# Upper_Board.net
KiCad netlist of a schematic drawn in Altium Designer
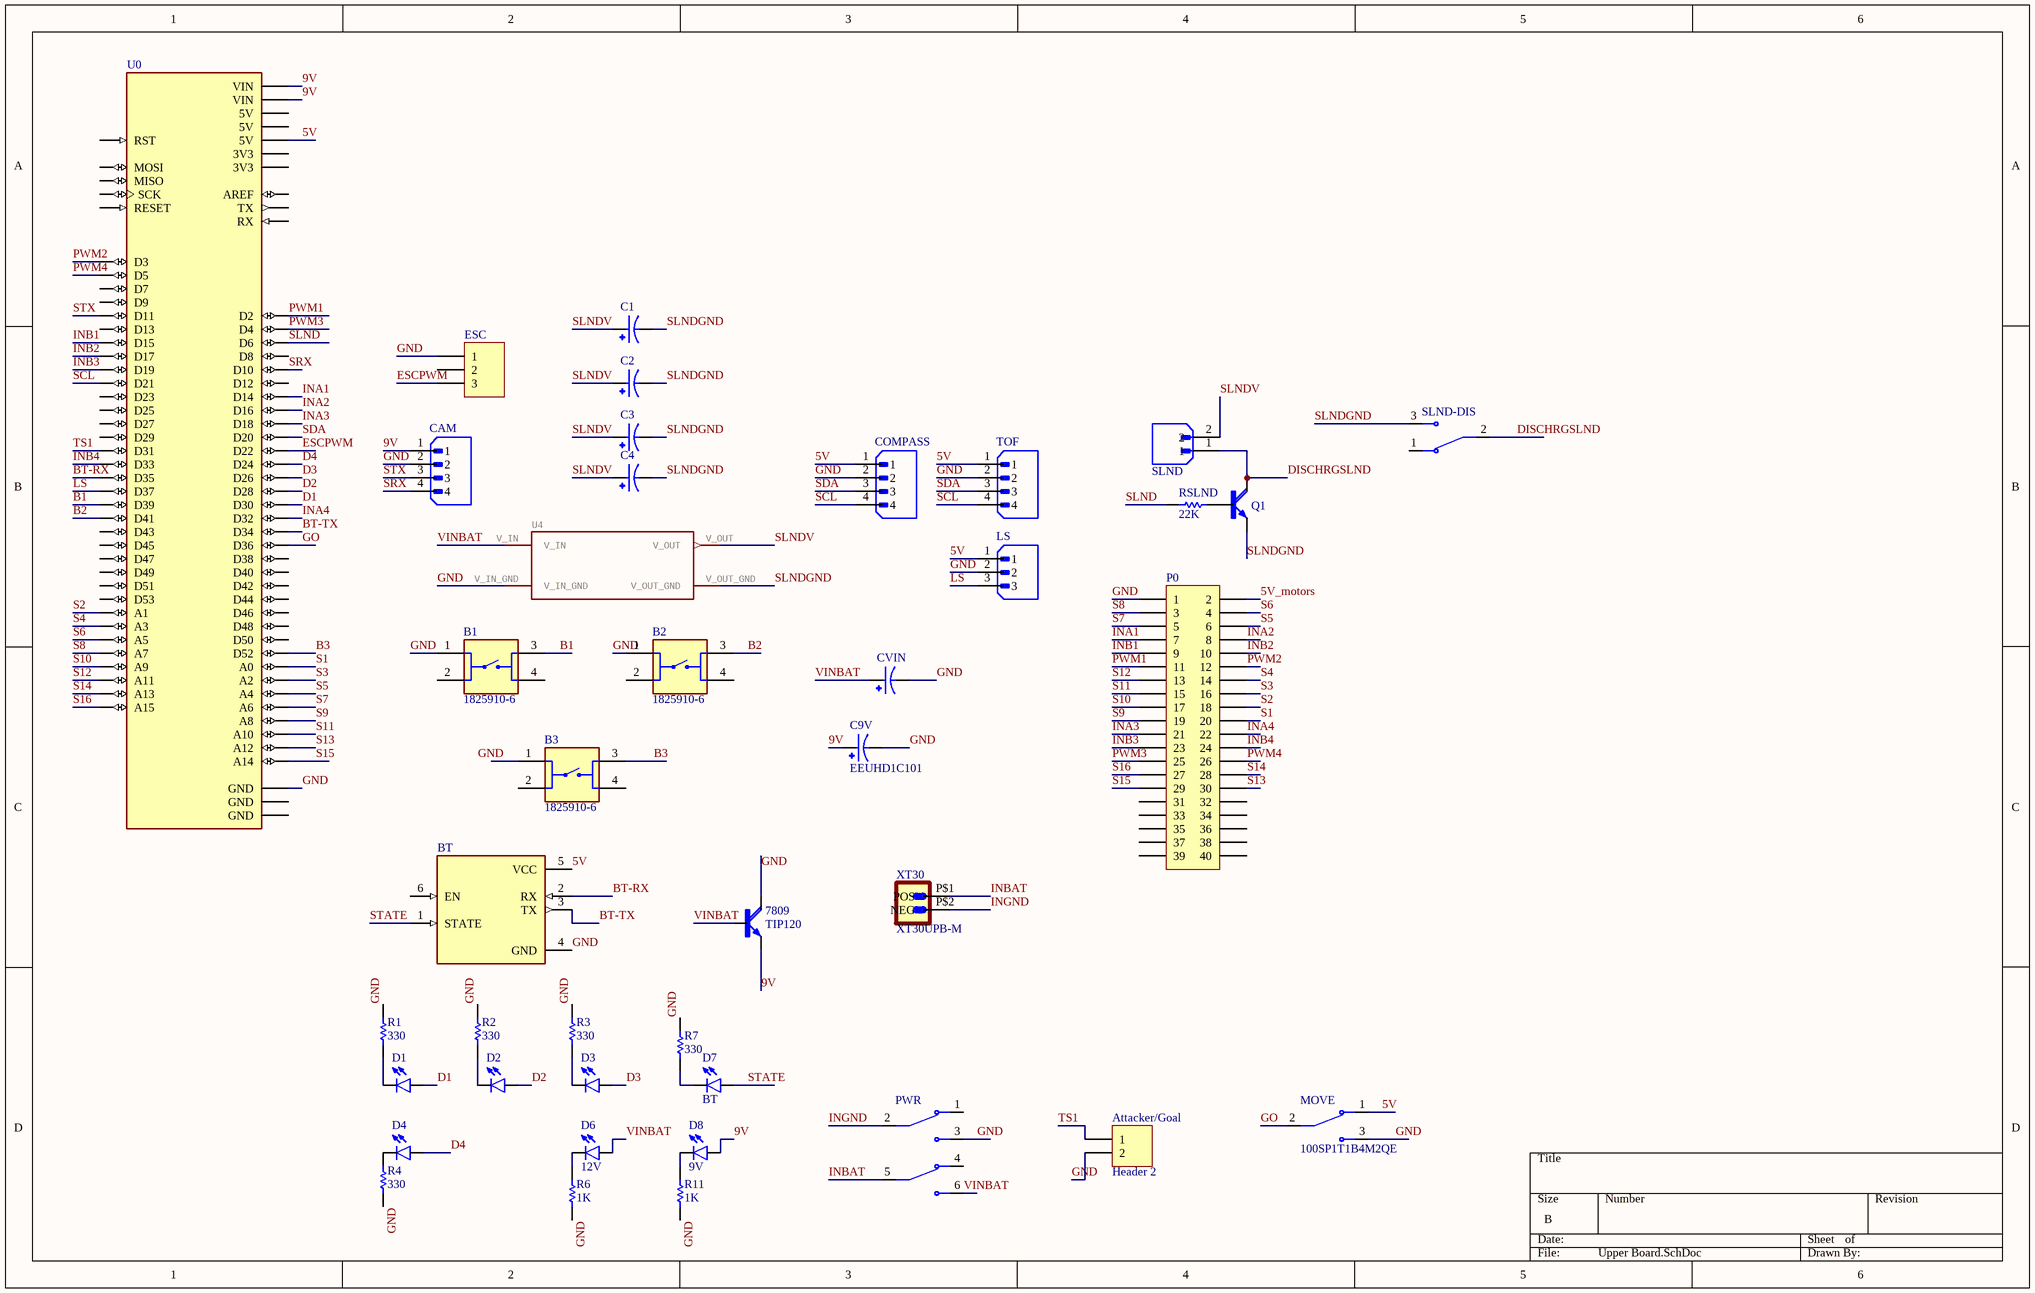
[diagram p0: Upper Board.SchDoc]

(export (version "E")
  (design (tool "Eeschema 10.0.6"))
  (components
    (comp (ref "7809")
      (value "TIP120")
      (footprint "TO220AH")
      (description "Bipolar _BJT_ Transistor NPN - Darlington 60V 5A 2W Through Hole TO-220-3")
      (fields (field (name "MF") "ON Semiconductor"))
      (libsource (lib "TIP120") (part "TIP120"))
    )
    (comp (ref "Attacker/Goal")
      (value "Header 2")
      (footprint "HDR1X2")
      (description "Header, 2-Pin")
      (fields (field (name "PUBLISHER") "Altium Limited"))
      (libsource (lib "Miscellaneous Connectors") (part "Header 2"))
    )
    (comp (ref "B1")
      (value "1825910-6")
      (footprint "SW_1825910-6-4")
      (description "Switch Push Button OFF (ON) SPST Round Button 0.05A 24VDC Momentary Contact PC Pins Thru-Hole")
      (fields (field (name "MF") "TE Connectivity") (field (name "DIGI-KEY_PART_NUMBER") "450-1650-ND"))
      (libsource (lib "pushbuttons-4pins") (part "1825910-6"))
    )
    (comp (ref "B2")
      (value "1825910-6")
      (footprint "SW_1825910-6-4")
      (description "Switch Push Button OFF (ON) SPST Round Button 0.05A 24VDC Momentary Contact PC Pins Thru-Hole")
      (fields (field (name "MF") "TE Connectivity") (field (name "DIGI-KEY_PART_NUMBER") "450-1650-ND"))
      (libsource (lib "pushbuttons-4pins") (part "1825910-6"))
    )
    (comp (ref "B3")
      (value "1825910-6")
      (footprint "SW_1825910-6-4")
      (description "Switch Push Button OFF (ON) SPST Round Button 0.05A 24VDC Momentary Contact PC Pins Thru-Hole")
      (fields (field (name "MF") "TE Connectivity") (field (name "DIGI-KEY_PART_NUMBER") "450-1650-ND"))
      (libsource (lib "pushbuttons-4pins") (part "1825910-6"))
    )
    (comp (ref "BT")
      (value "ZC142200")
      (footprint "MODULE_ZC142200")
      (description "1pc HC-05 6 Pin Wireless Bluetooth RF Transceiver Module Serial For Arduino")
      (libsource (lib "ZC142200") (part "ZC142200"))
    )
    (comp (ref "C1")
      (value "EEUHD1H222")
      (footprint "CAPPRD750W80D1600H3150")
      (description "2200ÂµF 50V Aluminum Electrolytic Capacitors Radial, Can 2000 Hrs @ 105Â°C")
      (fields (field (name "MF") "Panasonic"))
      (libsource (lib "CAP 2200uF") (part "EEUHD1H222"))
    )
    (comp (ref "C2")
      (value "EEUHD1H222")
      (footprint "CAPPRD750W80D1600H3150")
      (description "2200ÂµF 50V Aluminum Electrolytic Capacitors Radial, Can 2000 Hrs @ 105Â°C")
      (fields (field (name "MF") "Panasonic"))
      (libsource (lib "CAP 2200uF") (part "EEUHD1H222"))
    )
    (comp (ref "C3")
      (value "EEUHD1H222")
      (footprint "CAPPRD750W80D1600H3150")
      (description "2200ÂµF 50V Aluminum Electrolytic Capacitors Radial, Can 2000 Hrs @ 105Â°C")
      (fields (field (name "MF") "Panasonic"))
      (libsource (lib "CAP 2200uF") (part "EEUHD1H222"))
    )
    (comp (ref "C4")
      (value "EEUHD1H222")
      (footprint "CAPPRD750W80D1600H3150")
      (description "2200ÂµF 50V Aluminum Electrolytic Capacitors Radial, Can 2000 Hrs @ 105Â°C")
      (fields (field (name "MF") "Panasonic"))
      (libsource (lib "CAP 2200uF") (part "EEUHD1H222"))
    )
    (comp (ref "C9V")
      (value "EEUHD1C101")
      (footprint "CAPPRD250W50D500H1100")
      (description "CAP ALUM 100UF 20% 16V RADIAL")
      (fields (field (name "MF") "Panasonic"))
      (libsource (lib "100uf") (part "EEUHD1C101"))
    )
    (comp (ref "CAM")
      (value "B4B-XH-A(LF)(SN)")
      (footprint "JST_B4B-XH-A(LF)(SN)")
      (description "Connector Header Through Hole 4 position 0.098 (2.50mm)")
      (fields (field (name "MF") "JST Sales"))
      (libsource (lib "B4B-XH-A_LF__SN_") (part "B4B-XH-A(LF)(SN)"))
    )
    (comp (ref "COMPASS")
      (value "B4B-XH-A(LF)(SN)")
      (footprint "JST_B4B-XH-A(LF)(SN)")
      (description "Connector Header Through Hole 4 position 0.098 (2.50mm)")
      (fields (field (name "MF") "JST Sales"))
      (libsource (lib "B4B-XH-A_LF__SN_") (part "B4B-XH-A(LF)(SN)"))
    )
    (comp (ref "CVIN")
      (value "EEUFR1C102B")
      (footprint "CAPPRD500W60D1000H1600")
      (description "CAP ALUM 1000UF 20% 16V RADIAL")
      (fields (field (name "MF") "Panasonic") (field (name "MP") "EEU-FR1C102B"))
      (libsource (lib "EEUFR1C102B") (part "EEUFR1C102B"))
    )
    (comp (ref "D1")
      (value "TLLG4400")
      (footprint "LED3MM")
      (description "Green 569nm LED Indication - Discrete 1.9V Radial")
      (fields (field (name "MF") "Vishay Semiconductors"))
      (libsource (lib "TLLG4400") (part "TLLG4400"))
    )
    (comp (ref "D2")
      (value "TLLG4400")
      (footprint "LED3MM")
      (description "Green 569nm LED Indication - Discrete 1.9V Radial")
      (fields (field (name "MF") "Vishay Semiconductors"))
      (libsource (lib "TLLG4400") (part "TLLG4400"))
    )
    (comp (ref "D3")
      (value "TLLG4400")
      (footprint "LED3MM")
      (description "Green 569nm LED Indication - Discrete 1.9V Radial")
      (fields (field (name "MF") "Vishay Semiconductors"))
      (libsource (lib "TLLG4400") (part "TLLG4400"))
    )
    (comp (ref "D4")
      (value "TLLG4400")
      (footprint "LED3MM")
      (description "Green 569nm LED Indication - Discrete 1.9V Radial")
      (fields (field (name "MF") "Vishay Semiconductors"))
      (libsource (lib "TLLG4400") (part "TLLG4400"))
    )
    (comp (ref "D6")
      (value "12V")
      (footprint "LED3MM")
      (description "Green 569nm LED Indication - Discrete 1.9V Radial")
      (fields (field (name "MP") "TLLG4400") (field (name "MF") "Vishay Semiconductors"))
      (libsource (lib "TLLG4400") (part "TLLG4400"))
    )
    (comp (ref "D7")
      (value "BT")
      (footprint "LED3MM")
      (description "Green 569nm LED Indication - Discrete 1.9V Radial")
      (fields (field (name "MP") "TLLG4400") (field (name "MF") "Vishay Semiconductors"))
      (libsource (lib "TLLG4400") (part "TLLG4400"))
    )
    (comp (ref "D8")
      (value "9V")
      (footprint "LED3MM")
      (description "Green 569nm LED Indication - Discrete 1.9V Radial")
      (fields (field (name "MP") "TLLG4400") (field (name "MF") "Vishay Semiconductors"))
      (libsource (lib "TLLG4400") (part "TLLG4400"))
    )
    (comp (ref "ESC")
      (value "Header 3")
      (footprint "HDR1X3")
      (description "Header, 3-Pin")
      (fields (field (name "PUBLISHER") "Altium Limited"))
      (libsource (lib "Miscellaneous Connectors") (part "Header 3"))
    )
    (comp (ref "LS")
      (value "B3B-XH-A(LF)(SN)")
      (footprint "JST_B3B-XH-A(LF)(SN)")
      (description "Connector Header Through Hole 3 position 0.098 (2.50mm)")
      (fields (field (name "MF") "JST Sales"))
      (libsource (lib "B3B-XH-A_LF__SN_") (part "B3B-XH-A(LF)(SN)"))
    )
    (comp (ref "MOVE")
      (value "100SP1T1B4M2QE")
      (footprint "3_pin_toggle_switch")
      (description "Toggle Switch SPDT Through Hole")
      (libsource (lib "100SP1T1B4M2QE") (part "100SP1T1B4M2QE"))
    )
    (comp (ref "P0")
      (value "Header 20X2")
      (footprint "HDR2X20")
      (description "Header, 20-Pin, Dual row")
      (fields (field (name "PUBLISHER") "Altium Limited"))
      (libsource (lib "Miscellaneous Connectors") (part "Header 20X2"))
    )
    (comp (ref "PWR")
      (value "100DP1T1B1M2QEH")
      (footprint "SW_100DP1T1B1M2QEH")
      (libsource (lib "100DP1T1B1M2QEH") (part "100DP1T1B1M2QEH"))
    )
    (comp (ref "Q1")
      (value "TIP120")
      (footprint "TO220AH")
      (description "Bipolar _BJT_ Transistor NPN - Darlington 60V 5A 2W Through Hole TO-220-3")
      (fields (field (name "MF") "ON Semiconductor"))
      (libsource (lib "TIP120") (part "TIP120"))
    )
    (comp (ref "R1")
      (value "330")
      (footprint "AXIAL-0.3")
      (description "Resistor")
      (fields (field (name "PUBLISHER") "Altium Limited"))
      (libsource (lib "Miscellaneous Devices") (part "Res1"))
    )
    (comp (ref "R2")
      (value "330")
      (footprint "AXIAL-0.3")
      (description "Resistor")
      (fields (field (name "PUBLISHER") "Altium Limited"))
      (libsource (lib "Miscellaneous Devices") (part "Res1"))
    )
    (comp (ref "R3")
      (value "330")
      (footprint "AXIAL-0.3")
      (description "Resistor")
      (fields (field (name "PUBLISHER") "Altium Limited"))
      (libsource (lib "Miscellaneous Devices") (part "Res1"))
    )
    (comp (ref "R4")
      (value "330")
      (footprint "AXIAL-0.3")
      (description "Resistor")
      (fields (field (name "PUBLISHER") "Altium Limited"))
      (libsource (lib "Miscellaneous Devices") (part "Res1"))
    )
    (comp (ref "R6")
      (value "1K")
      (footprint "AXIAL-0.3")
      (description "Resistor")
      (fields (field (name "PUBLISHER") "Altium Limited"))
      (libsource (lib "Miscellaneous Devices") (part "Res1"))
    )
    (comp (ref "R7")
      (value "330")
      (footprint "AXIAL-0.3")
      (description "Resistor")
      (fields (field (name "PUBLISHER") "Altium Limited"))
      (libsource (lib "Miscellaneous Devices") (part "Res1"))
    )
    (comp (ref "R11")
      (value "1K")
      (footprint "AXIAL-0.3")
      (description "Resistor")
      (fields (field (name "PUBLISHER") "Altium Limited"))
      (libsource (lib "Miscellaneous Devices") (part "Res1"))
    )
    (comp (ref "RSLND")
      (value "22K")
      (footprint "AXIAL-0.3")
      (description "Resistor")
      (fields (field (name "PUBLISHER") "Altium Limited"))
      (libsource (lib "Miscellaneous Devices") (part "Res1"))
    )
    (comp (ref "SLND")
      (value "B2B-XH-A(LF)(SN)")
      (footprint "JST_B2B-XH-A(LF)(SN)")
      (description "Connector Header Through Hole 2 position 0.098 (2.50mm)")
      (fields (field (name "MF") "JST Sales"))
      (libsource (lib "JST Power 2 Pin Socket") (part "B2B-XH-A(LF)(SN)"))
    )
    (comp (ref "SLND-DIS")
      (value "100SP1T1B4M2QE")
      (footprint "3_pin_toggle_switch")
      (description "Toggle Switch SPDT Through Hole")
      (libsource (lib "100SP1T1B4M2QE") (part "100SP1T1B4M2QE"))
    )
    (comp (ref "TOF")
      (value "B4B-XH-A(LF)(SN)")
      (footprint "JST_B4B-XH-A(LF)(SN)")
      (description "Connector Header Through Hole 4 position 0.098 (2.50mm)")
      (fields (field (name "MF") "JST Sales"))
      (libsource (lib "B4B-XH-A_LF__SN_") (part "B4B-XH-A(LF)(SN)"))
    )
    (comp (ref "U0")
      (value "MEGA_PRO_EMBED_CH340G_/_ATMEGA2560")
      (footprint "MODULE_MEGA_PRO_EMBED_CH340G_/_ATMEGA2560")
      (description "Mega 2560 PRO (Embed) CH340G/ATmega2560-16AU")
      (libsource (lib "MEGA_PRO_EMBED_CH340G___ATMEGA2560") (part "MEGA_PRO_EMBED_CH340G_/_ATMEGA2560"))
    )
    (comp (ref "U4")
      (value "XL6009 Boost converter   Vin: 3-35V, 4A Vout: 5-35V, 2A Quiescent current: 18mA Switching frequency: 400KHz Ripple: 50mV Voltage regulation: 0.5% Size: 43 x 22 x 16mm")
      (footprint "XL6009_BOOST_MODULE")
      (libsource (lib "breakout-modules.Library") (part "XL6009_BOOST_MODULE"))
    )
    (comp (ref "XT30")
      (value "XT30UPB-M")
      (footprint "XT30UPB-M")
      (description "Socket; DC supply; XT30; male; PIN: 2; on PCBs; THT; yellow; 15A; 500V")
      (fields (field (name "MF") "amass"))
      (libsource (lib "XT30UPB-M") (part "XT30UPB-M"))
    )
  )
  (nets
    (net (code "1") (name "/5V") (class "Default")
      (node (ref "BT") (pin "5") (pinfunction "VCC_5") (pintype "power_in"))
      (node (ref "COMPASS") (pin "1") (pinfunction "1_1") (pintype "passive"))
      (node (ref "LS") (pin "1") (pinfunction "1_1") (pintype "passive"))
      (node (ref "MOVE") (pin "1") (pinfunction "1_1") (pintype "passive"))
      (node (ref "TOF") (pin "1") (pinfunction "1_1") (pintype "passive"))
      (node (ref "U0") (pin "5V_3") (pinfunction "5V_5V_3") (pintype "power_in"))
    )
    (net (code "2") (name "/5V_motors") (class "Default")
      (node (ref "P0") (pin "2") (pinfunction "2_2") (pintype "passive"))
    )
    (net (code "3") (name "/9V") (class "Default")
      (node (ref "7809") (pin "E") (pinfunction "E_E") (pintype "passive"))
      (node (ref "C9V") (pin "P") (pinfunction "P_P") (pintype "passive"))
      (node (ref "CAM") (pin "1") (pinfunction "1_1") (pintype "passive"))
      (node (ref "D8") (pin "A") (pinfunction "A_A") (pintype "passive"))
      (node (ref "U0") (pin "VIN_1") (pinfunction "VIN_VIN_1") (pintype "power_in"))
      (node (ref "U0") (pin "VIN_2") (pinfunction "VIN_VIN_2") (pintype "power_in"))
    )
    (net (code "4") (name "/B1") (class "Default")
      (node (ref "B1") (pin "3") (pinfunction "3_3") (pintype "passive"))
      (node (ref "U0") (pin "D39") (pinfunction "D39_D39") (pintype "bidirectional"))
    )
    (net (code "5") (name "/B2") (class "Default")
      (node (ref "B2") (pin "3") (pinfunction "3_3") (pintype "passive"))
      (node (ref "U0") (pin "D41") (pinfunction "D41_D41") (pintype "bidirectional"))
    )
    (net (code "6") (name "/B3") (class "Default")
      (node (ref "B3") (pin "3") (pinfunction "3_3") (pintype "passive"))
      (node (ref "U0") (pin "D52") (pinfunction "D52_D52") (pintype "bidirectional"))
    )
    (net (code "7") (name "/BT-RX") (class "Default")
      (node (ref "BT") (pin "2") (pinfunction "RX_2") (pintype "input"))
      (node (ref "U0") (pin "D35") (pinfunction "D35_D35") (pintype "bidirectional"))
    )
    (net (code "8") (name "/BT-TX") (class "Default")
      (node (ref "BT") (pin "3") (pinfunction "TX_3") (pintype "output"))
      (node (ref "U0") (pin "D34") (pinfunction "D34_D34") (pintype "bidirectional"))
    )
    (net (code "9") (name "/D1") (class "Default")
      (node (ref "D1") (pin "A") (pinfunction "A_A") (pintype "passive"))
      (node (ref "U0") (pin "D30") (pinfunction "D30_D30") (pintype "bidirectional"))
    )
    (net (code "10") (name "/D2") (class "Default")
      (node (ref "D2") (pin "A") (pinfunction "A_A") (pintype "passive"))
      (node (ref "U0") (pin "D28") (pinfunction "D28_D28") (pintype "bidirectional"))
    )
    (net (code "11") (name "/D3") (class "Default")
      (node (ref "D3") (pin "A") (pinfunction "A_A") (pintype "passive"))
      (node (ref "U0") (pin "D26") (pinfunction "D26_D26") (pintype "bidirectional"))
    )
    (net (code "12") (name "/D4") (class "Default")
      (node (ref "D4") (pin "A") (pinfunction "A_A") (pintype "passive"))
      (node (ref "U0") (pin "D24") (pinfunction "D24_D24") (pintype "bidirectional"))
    )
    (net (code "13") (name "/DISCHRGSLND") (class "Default")
      (node (ref "Q1") (pin "C") (pinfunction "C_C") (pintype "passive"))
      (node (ref "SLND") (pin "1") (pinfunction "1_1") (pintype "passive"))
      (node (ref "SLND-DIS") (pin "2") (pinfunction "2_2") (pintype "passive"))
    )
    (net (code "14") (name "/ESCPWM") (class "Default")
      (node (ref "ESC") (pin "3") (pinfunction "3_3") (pintype "passive"))
      (node (ref "U0") (pin "D22") (pinfunction "D22_D22") (pintype "bidirectional"))
    )
    (net (code "15") (name "/GND") (class "Default")
      (node (ref "7809") (pin "C") (pinfunction "C_C") (pintype "passive"))
      (node (ref "Attacker/Goal") (pin "2") (pinfunction "2_2") (pintype "passive"))
      (node (ref "B1") (pin "1") (pinfunction "1_1") (pintype "passive"))
      (node (ref "B2") (pin "1") (pinfunction "1_1") (pintype "passive"))
      (node (ref "B3") (pin "1") (pinfunction "1_1") (pintype "passive"))
      (node (ref "BT") (pin "4") (pinfunction "GND_4") (pintype "power_in"))
      (node (ref "C9V") (pin "N") (pinfunction "N_N") (pintype "passive"))
      (node (ref "CAM") (pin "2") (pinfunction "2_2") (pintype "passive"))
      (node (ref "COMPASS") (pin "2") (pinfunction "2_2") (pintype "passive"))
      (node (ref "CVIN") (pin "N") (pinfunction "N_N") (pintype "passive"))
      (node (ref "ESC") (pin "1") (pinfunction "1_1") (pintype "passive"))
      (node (ref "LS") (pin "2") (pinfunction "2_2") (pintype "passive"))
      (node (ref "MOVE") (pin "3") (pinfunction "3_3") (pintype "passive"))
      (node (ref "P0") (pin "1") (pinfunction "1_1") (pintype "passive"))
      (node (ref "PWR") (pin "3") (pinfunction "3_3") (pintype "passive"))
      (node (ref "R1") (pin "2") (pinfunction "2_2") (pintype "passive"))
      (node (ref "R11") (pin "2") (pinfunction "2_2") (pintype "passive"))
      (node (ref "R2") (pin "2") (pinfunction "2_2") (pintype "passive"))
      (node (ref "R3") (pin "2") (pinfunction "2_2") (pintype "passive"))
      (node (ref "R4") (pin "2") (pinfunction "2_2") (pintype "passive"))
      (node (ref "R6") (pin "2") (pinfunction "2_2") (pintype "passive"))
      (node (ref "R7") (pin "2") (pinfunction "2_2") (pintype "passive"))
      (node (ref "TOF") (pin "2") (pinfunction "2_2") (pintype "passive"))
      (node (ref "U0") (pin "GND_1") (pinfunction "GND_GND_1") (pintype "power_in"))
      (node (ref "U4") (pin "V_IN_GND") (pinfunction "V_IN_GND_V_IN_GND") (pintype "power_in"))
    )
    (net (code "16") (name "/GO") (class "Default")
      (node (ref "MOVE") (pin "2") (pinfunction "2_2") (pintype "passive"))
      (node (ref "U0") (pin "D36") (pinfunction "D36_D36") (pintype "bidirectional"))
    )
    (net (code "17") (name "/INA1") (class "Default")
      (node (ref "P0") (pin "7") (pinfunction "7_7") (pintype "passive"))
      (node (ref "U0") (pin "D14") (pinfunction "D14_D14") (pintype "bidirectional"))
    )
    (net (code "18") (name "/INA2") (class "Default")
      (node (ref "P0") (pin "8") (pinfunction "8_8") (pintype "passive"))
      (node (ref "U0") (pin "D16") (pinfunction "D16_D16") (pintype "bidirectional"))
    )
    (net (code "19") (name "/INA3") (class "Default")
      (node (ref "P0") (pin "21") (pinfunction "21_21") (pintype "passive"))
      (node (ref "U0") (pin "D18") (pinfunction "D18_D18") (pintype "bidirectional"))
    )
    (net (code "20") (name "/INA4") (class "Default")
      (node (ref "P0") (pin "22") (pinfunction "22_22") (pintype "passive"))
      (node (ref "U0") (pin "D32") (pinfunction "D32_D32") (pintype "bidirectional"))
    )
    (net (code "21") (name "/INB1") (class "Default")
      (node (ref "P0") (pin "9") (pinfunction "9_9") (pintype "passive"))
      (node (ref "U0") (pin "D15") (pinfunction "D15_D15") (pintype "bidirectional"))
    )
    (net (code "22") (name "/INB2") (class "Default")
      (node (ref "P0") (pin "10") (pinfunction "10_10") (pintype "passive"))
      (node (ref "U0") (pin "D17") (pinfunction "D17_D17") (pintype "bidirectional"))
    )
    (net (code "23") (name "/INB3") (class "Default")
      (node (ref "P0") (pin "23") (pinfunction "23_23") (pintype "passive"))
      (node (ref "U0") (pin "D19") (pinfunction "D19_D19") (pintype "bidirectional"))
    )
    (net (code "24") (name "/INB4") (class "Default")
      (node (ref "P0") (pin "24") (pinfunction "24_24") (pintype "passive"))
      (node (ref "U0") (pin "D33") (pinfunction "D33_D33") (pintype "bidirectional"))
    )
    (net (code "25") (name "/INBAT") (class "Default")
      (node (ref "PWR") (pin "5") (pinfunction "5_5") (pintype "passive"))
      (node (ref "XT30") (pin "P$1") (pinfunction "POS_P$1") (pintype "passive"))
    )
    (net (code "26") (name "/INGND") (class "Default")
      (node (ref "PWR") (pin "2") (pinfunction "2_2") (pintype "passive"))
      (node (ref "XT30") (pin "P$2") (pinfunction "NEG_P$2") (pintype "passive"))
    )
    (net (code "27") (name "/LS") (class "Default")
      (node (ref "LS") (pin "3") (pinfunction "3_3") (pintype "passive"))
      (node (ref "U0") (pin "D37") (pinfunction "D37_D37") (pintype "bidirectional"))
    )
    (net (code "28") (name "/PWM1") (class "Default")
      (node (ref "P0") (pin "11") (pinfunction "11_11") (pintype "passive"))
      (node (ref "U0") (pin "D2") (pinfunction "D2_D2") (pintype "bidirectional"))
    )
    (net (code "29") (name "/PWM2") (class "Default")
      (node (ref "P0") (pin "12") (pinfunction "12_12") (pintype "passive"))
      (node (ref "U0") (pin "D3") (pinfunction "D3_D3") (pintype "bidirectional"))
    )
    (net (code "30") (name "/PWM3") (class "Default")
      (node (ref "P0") (pin "25") (pinfunction "25_25") (pintype "passive"))
      (node (ref "U0") (pin "D4") (pinfunction "D4_D4") (pintype "bidirectional"))
    )
    (net (code "31") (name "/PWM4") (class "Default")
      (node (ref "P0") (pin "26") (pinfunction "26_26") (pintype "passive"))
      (node (ref "U0") (pin "D5") (pinfunction "D5_D5") (pintype "bidirectional"))
    )
    (net (code "32") (name "/S1") (class "Default")
      (node (ref "P0") (pin "20") (pinfunction "20_20") (pintype "passive"))
      (node (ref "U0") (pin "A0") (pinfunction "A0_A0") (pintype "bidirectional"))
    )
    (net (code "33") (name "/S2") (class "Default")
      (node (ref "P0") (pin "18") (pinfunction "18_18") (pintype "passive"))
      (node (ref "U0") (pin "A1") (pinfunction "A1_A1") (pintype "bidirectional"))
    )
    (net (code "34") (name "/S3") (class "Default")
      (node (ref "P0") (pin "16") (pinfunction "16_16") (pintype "passive"))
      (node (ref "U0") (pin "A2") (pinfunction "A2_A2") (pintype "bidirectional"))
    )
    (net (code "35") (name "/S4") (class "Default")
      (node (ref "P0") (pin "14") (pinfunction "14_14") (pintype "passive"))
      (node (ref "U0") (pin "A3") (pinfunction "A3_A3") (pintype "bidirectional"))
    )
    (net (code "36") (name "/S5") (class "Default")
      (node (ref "P0") (pin "6") (pinfunction "6_6") (pintype "passive"))
      (node (ref "U0") (pin "A4") (pinfunction "A4_A4") (pintype "bidirectional"))
    )
    (net (code "37") (name "/S6") (class "Default")
      (node (ref "P0") (pin "4") (pinfunction "4_4") (pintype "passive"))
      (node (ref "U0") (pin "A5") (pinfunction "A5_A5") (pintype "bidirectional"))
    )
    (net (code "38") (name "/S7") (class "Default")
      (node (ref "P0") (pin "5") (pinfunction "5_5") (pintype "passive"))
      (node (ref "U0") (pin "A6") (pinfunction "A6_A6") (pintype "bidirectional"))
    )
    (net (code "39") (name "/S8") (class "Default")
      (node (ref "P0") (pin "3") (pinfunction "3_3") (pintype "passive"))
      (node (ref "U0") (pin "A7") (pinfunction "A7_A7") (pintype "bidirectional"))
    )
    (net (code "40") (name "/S9") (class "Default")
      (node (ref "P0") (pin "19") (pinfunction "19_19") (pintype "passive"))
      (node (ref "U0") (pin "A8") (pinfunction "A8_A8") (pintype "bidirectional"))
    )
    (net (code "41") (name "/S10") (class "Default")
      (node (ref "P0") (pin "17") (pinfunction "17_17") (pintype "passive"))
      (node (ref "U0") (pin "A9") (pinfunction "A9_A9") (pintype "bidirectional"))
    )
    (net (code "42") (name "/S11") (class "Default")
      (node (ref "P0") (pin "15") (pinfunction "15_15") (pintype "passive"))
      (node (ref "U0") (pin "A10") (pinfunction "A10_A10") (pintype "bidirectional"))
    )
    (net (code "43") (name "/S12") (class "Default")
      (node (ref "P0") (pin "13") (pinfunction "13_13") (pintype "passive"))
      (node (ref "U0") (pin "A11") (pinfunction "A11_A11") (pintype "bidirectional"))
    )
    (net (code "44") (name "/S13") (class "Default")
      (node (ref "P0") (pin "30") (pinfunction "30_30") (pintype "passive"))
      (node (ref "U0") (pin "A12") (pinfunction "A12_A12") (pintype "bidirectional"))
    )
    (net (code "45") (name "/S14") (class "Default")
      (node (ref "P0") (pin "28") (pinfunction "28_28") (pintype "passive"))
      (node (ref "U0") (pin "A13") (pinfunction "A13_A13") (pintype "bidirectional"))
    )
    (net (code "46") (name "/S15") (class "Default")
      (node (ref "P0") (pin "29") (pinfunction "29_29") (pintype "passive"))
      (node (ref "U0") (pin "A14") (pinfunction "A14_A14") (pintype "bidirectional"))
    )
    (net (code "47") (name "/S16") (class "Default")
      (node (ref "P0") (pin "27") (pinfunction "27_27") (pintype "passive"))
      (node (ref "U0") (pin "A15") (pinfunction "A15_A15") (pintype "bidirectional"))
    )
    (net (code "48") (name "/SCL") (class "Default")
      (node (ref "COMPASS") (pin "4") (pinfunction "4_4") (pintype "passive"))
      (node (ref "TOF") (pin "4") (pinfunction "4_4") (pintype "passive"))
      (node (ref "U0") (pin "D21") (pinfunction "D21_D21") (pintype "bidirectional"))
    )
    (net (code "49") (name "/SDA") (class "Default")
      (node (ref "COMPASS") (pin "3") (pinfunction "3_3") (pintype "passive"))
      (node (ref "TOF") (pin "3") (pinfunction "3_3") (pintype "passive"))
      (node (ref "U0") (pin "D20") (pinfunction "D20_D20") (pintype "bidirectional"))
    )
    (net (code "50") (name "/SLND") (class "Default")
      (node (ref "RSLND") (pin "1") (pinfunction "1_1") (pintype "passive"))
      (node (ref "U0") (pin "D6") (pinfunction "D6_D6") (pintype "bidirectional"))
    )
    (net (code "51") (name "/SLNDGND") (class "Default")
      (node (ref "C1") (pin "N") (pinfunction "N_N") (pintype "passive"))
      (node (ref "C2") (pin "N") (pinfunction "N_N") (pintype "passive"))
      (node (ref "C3") (pin "N") (pinfunction "N_N") (pintype "passive"))
      (node (ref "C4") (pin "N") (pinfunction "N_N") (pintype "passive"))
      (node (ref "Q1") (pin "E") (pinfunction "E_E") (pintype "passive"))
      (node (ref "SLND-DIS") (pin "3") (pinfunction "3_3") (pintype "passive"))
      (node (ref "U4") (pin "V_OUT_GND") (pinfunction "V_OUT_GND_V_OUT_GND") (pintype "power_in"))
    )
    (net (code "52") (name "/SLNDV") (class "Default")
      (node (ref "C1") (pin "P") (pinfunction "P_P") (pintype "passive"))
      (node (ref "C2") (pin "P") (pinfunction "P_P") (pintype "passive"))
      (node (ref "C3") (pin "P") (pinfunction "P_P") (pintype "passive"))
      (node (ref "C4") (pin "P") (pinfunction "P_P") (pintype "passive"))
      (node (ref "SLND") (pin "2") (pinfunction "2_2") (pintype "passive"))
      (node (ref "U4") (pin "V_OUT") (pinfunction "V_OUT_V_OUT") (pintype "output"))
    )
    (net (code "53") (name "/SRX") (class "Default")
      (node (ref "CAM") (pin "4") (pinfunction "4_4") (pintype "passive"))
      (node (ref "U0") (pin "D10") (pinfunction "D10_D10") (pintype "bidirectional"))
    )
    (net (code "54") (name "/STATE") (class "Default")
      (node (ref "BT") (pin "1") (pinfunction "STATE_1") (pintype "input"))
      (node (ref "D7") (pin "A") (pinfunction "A_A") (pintype "passive"))
    )
    (net (code "55") (name "/STX") (class "Default")
      (node (ref "CAM") (pin "3") (pinfunction "3_3") (pintype "passive"))
      (node (ref "U0") (pin "D11") (pinfunction "D11_D11") (pintype "bidirectional"))
    )
    (net (code "56") (name "/TS1") (class "Default")
      (node (ref "Attacker/Goal") (pin "1") (pinfunction "1_1") (pintype "passive"))
      (node (ref "U0") (pin "D31") (pinfunction "D31_D31") (pintype "bidirectional"))
    )
    (net (code "57") (name "/VINBAT") (class "Default")
      (node (ref "7809") (pin "B") (pinfunction "B_B") (pintype "passive"))
      (node (ref "CVIN") (pin "P") (pinfunction "P_P") (pintype "passive"))
      (node (ref "D6") (pin "A") (pinfunction "A_A") (pintype "passive"))
      (node (ref "PWR") (pin "6") (pinfunction "6_6") (pintype "passive"))
      (node (ref "U4") (pin "V_IN") (pinfunction "V_IN_V_IN") (pintype "power_in"))
    )
    (net (code "58") (name "Net-(D1-C)") (class "Default")
      (node (ref "D1") (pin "K") (pinfunction "C_K") (pintype "passive"))
      (node (ref "R1") (pin "1") (pinfunction "1_1") (pintype "passive"))
    )
    (net (code "59") (name "Net-(D2-C)") (class "Default")
      (node (ref "D2") (pin "K") (pinfunction "C_K") (pintype "passive"))
      (node (ref "R2") (pin "1") (pinfunction "1_1") (pintype "passive"))
    )
    (net (code "60") (name "Net-(D3-C)") (class "Default")
      (node (ref "D3") (pin "K") (pinfunction "C_K") (pintype "passive"))
      (node (ref "R3") (pin "1") (pinfunction "1_1") (pintype "passive"))
    )
    (net (code "61") (name "Net-(D4-C)") (class "Default")
      (node (ref "D4") (pin "K") (pinfunction "C_K") (pintype "passive"))
      (node (ref "R4") (pin "1") (pinfunction "1_1") (pintype "passive"))
    )
    (net (code "62") (name "Net-(D6-C)") (class "Default")
      (node (ref "D6") (pin "K") (pinfunction "C_K") (pintype "passive"))
      (node (ref "R6") (pin "1") (pinfunction "1_1") (pintype "passive"))
    )
    (net (code "63") (name "Net-(D7-C)") (class "Default")
      (node (ref "D7") (pin "K") (pinfunction "C_K") (pintype "passive"))
      (node (ref "R7") (pin "1") (pinfunction "1_1") (pintype "passive"))
    )
    (net (code "64") (name "Net-(D8-C)") (class "Default")
      (node (ref "D8") (pin "K") (pinfunction "C_K") (pintype "passive"))
      (node (ref "R11") (pin "1") (pinfunction "1_1") (pintype "passive"))
    )
    (net (code "65") (name "Net-(Q1-PadB)") (class "Default")
      (node (ref "Q1") (pin "B") (pinfunction "B_B") (pintype "passive"))
      (node (ref "RSLND") (pin "2") (pinfunction "2_2") (pintype "passive"))
    )
    (net (code "66") (name "unconnected-(B1-Pad2)") (class "Default")
      (node (ref "B1") (pin "2") (pinfunction "2_2") (pintype "passive"))
    )
    (net (code "67") (name "unconnected-(B1-Pad4)") (class "Default")
      (node (ref "B1") (pin "4") (pinfunction "4_4") (pintype "passive"))
    )
    (net (code "68") (name "unconnected-(B2-Pad2)") (class "Default")
      (node (ref "B2") (pin "2") (pinfunction "2_2") (pintype "passive"))
    )
    (net (code "69") (name "unconnected-(B2-Pad4)") (class "Default")
      (node (ref "B2") (pin "4") (pinfunction "4_4") (pintype "passive"))
    )
    (net (code "70") (name "unconnected-(B3-Pad2)") (class "Default")
      (node (ref "B3") (pin "2") (pinfunction "2_2") (pintype "passive"))
    )
    (net (code "71") (name "unconnected-(B3-Pad4)") (class "Default")
      (node (ref "B3") (pin "4") (pinfunction "4_4") (pintype "passive"))
    )
    (net (code "72") (name "unconnected-(BT-EN-Pad6)") (class "Default")
      (node (ref "BT") (pin "6") (pinfunction "EN_6") (pintype "input"))
    )
    (net (code "73") (name "unconnected-(ESC-Pad2)") (class "Default")
      (node (ref "ESC") (pin "2") (pinfunction "2_2") (pintype "passive"))
    )
    (net (code "74") (name "unconnected-(P0-Pad31)") (class "Default")
      (node (ref "P0") (pin "31") (pinfunction "31_31") (pintype "passive"))
    )
    (net (code "75") (name "unconnected-(P0-Pad32)") (class "Default")
      (node (ref "P0") (pin "32") (pinfunction "32_32") (pintype "passive"))
    )
    (net (code "76") (name "unconnected-(P0-Pad33)") (class "Default")
      (node (ref "P0") (pin "33") (pinfunction "33_33") (pintype "passive"))
    )
    (net (code "77") (name "unconnected-(P0-Pad34)") (class "Default")
      (node (ref "P0") (pin "34") (pinfunction "34_34") (pintype "passive"))
    )
    (net (code "78") (name "unconnected-(P0-Pad35)") (class "Default")
      (node (ref "P0") (pin "35") (pinfunction "35_35") (pintype "passive"))
    )
    (net (code "79") (name "unconnected-(P0-Pad36)") (class "Default")
      (node (ref "P0") (pin "36") (pinfunction "36_36") (pintype "passive"))
    )
    (net (code "80") (name "unconnected-(P0-Pad37)") (class "Default")
      (node (ref "P0") (pin "37") (pinfunction "37_37") (pintype "passive"))
    )
    (net (code "81") (name "unconnected-(P0-Pad38)") (class "Default")
      (node (ref "P0") (pin "38") (pinfunction "38_38") (pintype "passive"))
    )
    (net (code "82") (name "unconnected-(P0-Pad39)") (class "Default")
      (node (ref "P0") (pin "39") (pinfunction "39_39") (pintype "passive"))
    )
    (net (code "83") (name "unconnected-(P0-Pad40)") (class "Default")
      (node (ref "P0") (pin "40") (pinfunction "40_40") (pintype "passive"))
    )
    (net (code "84") (name "unconnected-(PWR-Pad1)") (class "Default")
      (node (ref "PWR") (pin "1") (pinfunction "1_1") (pintype "passive"))
    )
    (net (code "85") (name "unconnected-(PWR-Pad4)") (class "Default")
      (node (ref "PWR") (pin "4") (pinfunction "4_4") (pintype "passive"))
    )
    (net (code "86") (name "unconnected-(SLND-DIS-Pad1)") (class "Default")
      (node (ref "SLND-DIS") (pin "1") (pinfunction "1_1") (pintype "passive"))
    )
    (net (code "87") (name "unconnected-(U0-3V3-Pad3V3_1)") (class "Default")
      (node (ref "U0") (pin "3V3_1") (pinfunction "3V3_3V3_1") (pintype "power_in"))
    )
    (net (code "88") (name "unconnected-(U0-3V3-Pad3V3_2)") (class "Default")
      (node (ref "U0") (pin "3V3_2") (pinfunction "3V3_3V3_2") (pintype "power_in"))
    )
    (net (code "89") (name "unconnected-(U0-5V-Pad5V_1)") (class "Default")
      (node (ref "U0") (pin "5V_1") (pinfunction "5V_5V_1") (pintype "power_in"))
    )
    (net (code "90") (name "unconnected-(U0-5V-Pad5V_2)") (class "Default")
      (node (ref "U0") (pin "5V_2") (pinfunction "5V_5V_2") (pintype "power_in"))
    )
    (net (code "91") (name "unconnected-(U0-GND-PadGND_2)") (class "Default")
      (node (ref "U0") (pin "GND_2") (pinfunction "GND_GND_2") (pintype "power_in"))
    )
    (net (code "92") (name "unconnected-(U0-GND-PadGND_3)") (class "Default")
      (node (ref "U0") (pin "GND_3") (pinfunction "GND_GND_3") (pintype "power_in"))
    )
    (net (code "93") (name "unconnected-(U0-PadAREF)") (class "Default")
      (node (ref "U0") (pin "AREF") (pinfunction "AREF_AREF") (pintype "bidirectional"))
    )
    (net (code "94") (name "unconnected-(U0-PadD7)") (class "Default")
      (node (ref "U0") (pin "D7") (pinfunction "D7_D7") (pintype "bidirectional"))
    )
    (net (code "95") (name "unconnected-(U0-PadD8)") (class "Default")
      (node (ref "U0") (pin "D8") (pinfunction "D8_D8") (pintype "bidirectional"))
    )
    (net (code "96") (name "unconnected-(U0-PadD9)") (class "Default")
      (node (ref "U0") (pin "D9") (pinfunction "D9_D9") (pintype "bidirectional"))
    )
    (net (code "97") (name "unconnected-(U0-PadD12)") (class "Default")
      (node (ref "U0") (pin "D12") (pinfunction "D12_D12") (pintype "bidirectional"))
    )
    (net (code "98") (name "unconnected-(U0-PadD13)") (class "Default")
      (node (ref "U0") (pin "D13") (pinfunction "D13_D13") (pintype "bidirectional"))
    )
    (net (code "99") (name "unconnected-(U0-PadD23)") (class "Default")
      (node (ref "U0") (pin "D23") (pinfunction "D23_D23") (pintype "bidirectional"))
    )
    (net (code "100") (name "unconnected-(U0-PadD25)") (class "Default")
      (node (ref "U0") (pin "D25") (pinfunction "D25_D25") (pintype "bidirectional"))
    )
    (net (code "101") (name "unconnected-(U0-PadD27)") (class "Default")
      (node (ref "U0") (pin "D27") (pinfunction "D27_D27") (pintype "bidirectional"))
    )
    (net (code "102") (name "unconnected-(U0-PadD29)") (class "Default")
      (node (ref "U0") (pin "D29") (pinfunction "D29_D29") (pintype "bidirectional"))
    )
    (net (code "103") (name "unconnected-(U0-PadD38)") (class "Default")
      (node (ref "U0") (pin "D38") (pinfunction "D38_D38") (pintype "bidirectional"))
    )
    (net (code "104") (name "unconnected-(U0-PadD40)") (class "Default")
      (node (ref "U0") (pin "D40") (pinfunction "D40_D40") (pintype "bidirectional"))
    )
    (net (code "105") (name "unconnected-(U0-PadD42)") (class "Default")
      (node (ref "U0") (pin "D42") (pinfunction "D42_D42") (pintype "bidirectional"))
    )
    (net (code "106") (name "unconnected-(U0-PadD43)") (class "Default")
      (node (ref "U0") (pin "D43") (pinfunction "D43_D43") (pintype "bidirectional"))
    )
    (net (code "107") (name "unconnected-(U0-PadD44)") (class "Default")
      (node (ref "U0") (pin "D44") (pinfunction "D44_D44") (pintype "bidirectional"))
    )
    (net (code "108") (name "unconnected-(U0-PadD45)") (class "Default")
      (node (ref "U0") (pin "D45") (pinfunction "D45_D45") (pintype "bidirectional"))
    )
    (net (code "109") (name "unconnected-(U0-PadD46)") (class "Default")
      (node (ref "U0") (pin "D46") (pinfunction "D46_D46") (pintype "bidirectional"))
    )
    (net (code "110") (name "unconnected-(U0-PadD47)") (class "Default")
      (node (ref "U0") (pin "D47") (pinfunction "D47_D47") (pintype "bidirectional"))
    )
    (net (code "111") (name "unconnected-(U0-PadD48)") (class "Default")
      (node (ref "U0") (pin "D48") (pinfunction "D48_D48") (pintype "bidirectional"))
    )
    (net (code "112") (name "unconnected-(U0-PadD49)") (class "Default")
      (node (ref "U0") (pin "D49") (pinfunction "D49_D49") (pintype "bidirectional"))
    )
    (net (code "113") (name "unconnected-(U0-PadD50)") (class "Default")
      (node (ref "U0") (pin "D50") (pinfunction "D50_D50") (pintype "bidirectional"))
    )
    (net (code "114") (name "unconnected-(U0-PadD51)") (class "Default")
      (node (ref "U0") (pin "D51") (pinfunction "D51_D51") (pintype "bidirectional"))
    )
    (net (code "115") (name "unconnected-(U0-PadD53)") (class "Default")
      (node (ref "U0") (pin "D53") (pinfunction "D53_D53") (pintype "bidirectional"))
    )
    (net (code "116") (name "unconnected-(U0-PadMISO)") (class "Default")
      (node (ref "U0") (pin "MISO") (pinfunction "MISO_MISO") (pintype "bidirectional"))
    )
    (net (code "117") (name "unconnected-(U0-PadMOSI)") (class "Default")
      (node (ref "U0") (pin "MOSI") (pinfunction "MOSI_MOSI") (pintype "bidirectional"))
    )
    (net (code "118") (name "unconnected-(U0-PadRESET)") (class "Default")
      (node (ref "U0") (pin "RESET") (pinfunction "RESET_RESET") (pintype "input"))
    )
    (net (code "119") (name "unconnected-(U0-PadRST)") (class "Default")
      (node (ref "U0") (pin "RST") (pinfunction "RST_RST") (pintype "input"))
    )
    (net (code "120") (name "unconnected-(U0-PadRX)") (class "Default")
      (node (ref "U0") (pin "RX") (pinfunction "RX_RX") (pintype "input"))
    )
    (net (code "121") (name "unconnected-(U0-PadSCK)") (class "Default")
      (node (ref "U0") (pin "SCK") (pinfunction "SCK_SCK") (pintype "bidirectional"))
    )
    (net (code "122") (name "unconnected-(U0-PadTX)") (class "Default")
      (node (ref "U0") (pin "TX") (pinfunction "TX_TX") (pintype "output"))
    )
  )
)
